# LTC_PowerStation.net
KiCad netlist of a schematic drawn in EAGLE
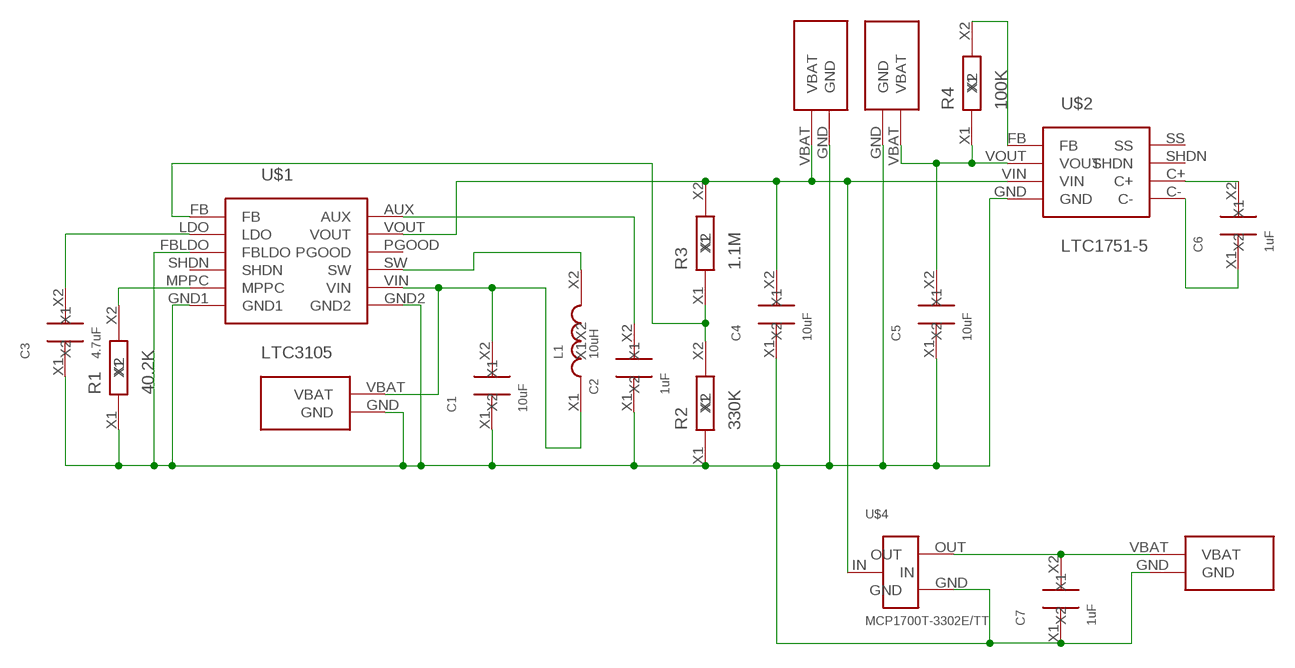
[diagram p0: schematic, sheet 1]

(export (version "E")
  (design (tool "Eeschema 10.0.6"))
  (components
    (comp (ref "C1")
      (value "10uF")
      (footprint "eagle-import:SMD_2.1X1.25")
      (libsource (lib "eagle-import") (part "C_SMD_2.1X1.25"))
    )
    (comp (ref "C2")
      (value "1uF")
      (footprint "eagle-import:SMD_2.1X1.25")
      (libsource (lib "eagle-import") (part "C_SMD_2.1X1.25"))
    )
    (comp (ref "C3")
      (value "4.7uF")
      (footprint "eagle-import:SMD_2.1X1.25")
      (libsource (lib "eagle-import") (part "C_SMD_2.1X1.25"))
    )
    (comp (ref "C4")
      (value "10uF")
      (footprint "eagle-import:SMD_2.1X1.25")
      (libsource (lib "eagle-import") (part "C_SMD_2.1X1.25"))
    )
    (comp (ref "C5")
      (value "10uF")
      (footprint "eagle-import:SMD_2.1X1.25")
      (libsource (lib "eagle-import") (part "C_SMD_2.1X1.25"))
    )
    (comp (ref "C6")
      (value "1uF")
      (footprint "eagle-import:SMD_2.1X1.25")
      (libsource (lib "eagle-import") (part "C_SMD_2.1X1.25"))
    )
    (comp (ref "C7")
      (value "1uF")
      (footprint "eagle-import:SMD_2.1X1.25")
      (libsource (lib "eagle-import") (part "C_SMD_2.1X1.25"))
    )
    (comp (ref "L1")
      (value "10uH")
      (footprint "eagle-import:SMD_2.1X1.25")
      (libsource (lib "eagle-import") (part "L_SMD_2.1X1.25"))
    )
    (comp (ref "R1")
      (value "40.2K")
      (footprint "eagle-import:SMD_2.1X1.25")
      (libsource (lib "eagle-import") (part "R_SMD_2.1X1.25"))
    )
    (comp (ref "R2")
      (value "330K")
      (footprint "eagle-import:SMD_2.1X1.25")
      (libsource (lib "eagle-import") (part "R_SMD_2.1X1.25"))
    )
    (comp (ref "R3")
      (value "1.1M")
      (footprint "eagle-import:SMD_2.1X1.25")
      (libsource (lib "eagle-import") (part "R_SMD_2.1X1.25"))
    )
    (comp (ref "R4")
      (value "100K")
      (footprint "eagle-import:SMD_2.1X1.25")
      (libsource (lib "eagle-import") (part "R_SMD_2.1X1.25"))
    )
    (comp (ref "U$1")
      (value "LTC3105")
      (footprint "eagle-import:LTC3105")
      (libsource (lib "eagle-import") (part "LTC3105"))
    )
    (comp (ref "U$2")
      (value "LTC1751-5")
      (footprint "eagle-import:LTC1751-5")
      (libsource (lib "eagle-import") (part "LTC1751-5"))
    )
    (comp (ref "U$3")
      (value "BAT_PLUG")
      (footprint "eagle-import:BAT_PLUG")
      (libsource (lib "eagle-import") (part "BAT_PLUG"))
    )
    (comp (ref "U$4")
      (value "MCP1700T-3302E/TT")
      (footprint "eagle-import:MCP1700T-3302E_TT")
      (libsource (lib "eagle-import") (part "MCP1700T-3302E/TT"))
    )
    (comp (ref "U$5")
      (value "BAT_PLUG")
      (footprint "eagle-import:BAT_PLUG")
      (libsource (lib "eagle-import") (part "BAT_PLUG"))
    )
    (comp (ref "U$10")
      (value "BAT_PLUG")
      (footprint "eagle-import:BAT_PLUG")
      (libsource (lib "eagle-import") (part "BAT_PLUG"))
    )
    (comp (ref "U$11")
      (value "BAT_PLUG")
      (footprint "eagle-import:BAT_PLUG")
      (libsource (lib "eagle-import") (part "BAT_PLUG"))
    )
  )
  (nets
    (net (code "1") (name "Net-(C1-PadX1)") (class "Default")
      (node (ref "C1") (pin "X1") (pinfunction "X1_X1") (pintype "bidirectional"))
      (node (ref "C2") (pin "X1") (pinfunction "X1_X1") (pintype "bidirectional"))
      (node (ref "C3") (pin "X1") (pinfunction "X1_X1") (pintype "bidirectional"))
      (node (ref "C4") (pin "X1") (pinfunction "X1_X1") (pintype "bidirectional"))
      (node (ref "C5") (pin "X1") (pinfunction "X1_X1") (pintype "bidirectional"))
      (node (ref "C7") (pin "X1") (pinfunction "X1_X1") (pintype "bidirectional"))
      (node (ref "R1") (pin "X1") (pinfunction "X1_X1") (pintype "bidirectional"))
      (node (ref "R2") (pin "X1") (pinfunction "X1_X1") (pintype "bidirectional"))
      (node (ref "U$1") (pin "FBLDO") (pinfunction "FBLDO_FBLDO") (pintype "bidirectional"))
      (node (ref "U$1") (pin "GND1") (pinfunction "GND1_GND1") (pintype "bidirectional"))
      (node (ref "U$1") (pin "GND2") (pinfunction "GND2_GND2") (pintype "bidirectional"))
      (node (ref "U$10") (pin "GND") (pinfunction "GND_GND") (pintype "bidirectional"))
      (node (ref "U$11") (pin "GND") (pinfunction "GND_GND") (pintype "bidirectional"))
      (node (ref "U$2") (pin "GND") (pinfunction "GND_GND") (pintype "bidirectional"))
      (node (ref "U$3") (pin "GND") (pinfunction "GND_GND") (pintype "bidirectional"))
      (node (ref "U$4") (pin "GND") (pinfunction "GND_GND") (pintype "bidirectional"))
      (node (ref "U$5") (pin "GND") (pinfunction "GND_GND") (pintype "bidirectional"))
    )
    (net (code "2") (name "Net-(C1-PadX2)") (class "Default")
      (node (ref "C1") (pin "X2") (pinfunction "X2_X2") (pintype "bidirectional"))
      (node (ref "L1") (pin "X1") (pinfunction "X1_X1") (pintype "bidirectional"))
      (node (ref "U$1") (pin "VIN") (pinfunction "VIN_VIN") (pintype "bidirectional"))
      (node (ref "U$10") (pin "VBAT") (pinfunction "VBAT_VBAT") (pintype "bidirectional"))
    )
    (net (code "3") (name "Net-(C2-PadX2)") (class "Default")
      (node (ref "C2") (pin "X2") (pinfunction "X2_X2") (pintype "bidirectional"))
      (node (ref "U$1") (pin "AUX") (pinfunction "AUX_AUX") (pintype "bidirectional"))
    )
    (net (code "4") (name "Net-(C3-PadX2)") (class "Default")
      (node (ref "C3") (pin "X2") (pinfunction "X2_X2") (pintype "bidirectional"))
      (node (ref "U$1") (pin "LDO") (pinfunction "LDO_LDO") (pintype "bidirectional"))
    )
    (net (code "5") (name "Net-(C4-PadX2)") (class "Default")
      (node (ref "C4") (pin "X2") (pinfunction "X2_X2") (pintype "bidirectional"))
      (node (ref "R3") (pin "X2") (pinfunction "X2_X2") (pintype "bidirectional"))
      (node (ref "U$1") (pin "VOUT") (pinfunction "VOUT_VOUT") (pintype "bidirectional"))
      (node (ref "U$11") (pin "VBAT") (pinfunction "VBAT_VBAT") (pintype "bidirectional"))
      (node (ref "U$2") (pin "VIN") (pinfunction "VIN_VIN") (pintype "bidirectional"))
      (node (ref "U$4") (pin "IN") (pinfunction "IN_IN") (pintype "bidirectional"))
    )
    (net (code "6") (name "Net-(C5-PadX2)") (class "Default")
      (node (ref "C5") (pin "X2") (pinfunction "X2_X2") (pintype "bidirectional"))
      (node (ref "R4") (pin "X1") (pinfunction "X1_X1") (pintype "bidirectional"))
      (node (ref "U$2") (pin "VOUT") (pinfunction "VOUT_VOUT") (pintype "bidirectional"))
      (node (ref "U$3") (pin "VBAT") (pinfunction "VBAT_VBAT") (pintype "bidirectional"))
    )
    (net (code "7") (name "Net-(C6-PadX1)") (class "Default")
      (node (ref "C6") (pin "X1") (pinfunction "X1_X1") (pintype "bidirectional"))
      (node (ref "U$2") (pin "C-") (pinfunction "C-_C-") (pintype "bidirectional"))
    )
    (net (code "8") (name "Net-(C6-PadX2)") (class "Default")
      (node (ref "C6") (pin "X2") (pinfunction "X2_X2") (pintype "bidirectional"))
      (node (ref "U$2") (pin "C+") (pinfunction "C+_C+") (pintype "bidirectional"))
    )
    (net (code "9") (name "Net-(C7-PadX2)") (class "Default")
      (node (ref "C7") (pin "X2") (pinfunction "X2_X2") (pintype "bidirectional"))
      (node (ref "U$4") (pin "OUT") (pinfunction "OUT_OUT") (pintype "bidirectional"))
      (node (ref "U$5") (pin "VBAT") (pinfunction "VBAT_VBAT") (pintype "bidirectional"))
    )
    (net (code "10") (name "Net-(L1-PadX2)") (class "Default")
      (node (ref "L1") (pin "X2") (pinfunction "X2_X2") (pintype "bidirectional"))
      (node (ref "U$1") (pin "SW") (pinfunction "SW_SW") (pintype "bidirectional"))
    )
    (net (code "11") (name "Net-(R1-PadX2)") (class "Default")
      (node (ref "R1") (pin "X2") (pinfunction "X2_X2") (pintype "bidirectional"))
      (node (ref "U$1") (pin "MPPC") (pinfunction "MPPC_MPPC") (pintype "bidirectional"))
    )
    (net (code "12") (name "Net-(R2-PadX2)") (class "Default")
      (node (ref "R2") (pin "X2") (pinfunction "X2_X2") (pintype "bidirectional"))
      (node (ref "R3") (pin "X1") (pinfunction "X1_X1") (pintype "bidirectional"))
      (node (ref "U$1") (pin "FB") (pinfunction "FB_FB") (pintype "bidirectional"))
    )
    (net (code "13") (name "Net-(R4-PadX2)") (class "Default")
      (node (ref "R4") (pin "X2") (pinfunction "X2_X2") (pintype "bidirectional"))
      (node (ref "U$2") (pin "FB") (pinfunction "FB_FB") (pintype "bidirectional"))
    )
    (net (code "14") (name "unconnected-(U$1-PadPGOOD)") (class "Default")
      (node (ref "U$1") (pin "PGOOD") (pinfunction "PGOOD_PGOOD") (pintype "bidirectional"))
    )
    (net (code "15") (name "unconnected-(U$1-PadSHDN)") (class "Default")
      (node (ref "U$1") (pin "SHDN") (pinfunction "SHDN_SHDN") (pintype "bidirectional"))
    )
    (net (code "16") (name "unconnected-(U$2-PadSHDN)") (class "Default")
      (node (ref "U$2") (pin "SHDN") (pinfunction "SHDN_SHDN") (pintype "bidirectional"))
    )
    (net (code "17") (name "unconnected-(U$2-PadSS)") (class "Default")
      (node (ref "U$2") (pin "SS") (pinfunction "SS_SS") (pintype "bidirectional"))
    )
  )
)
